# TermWylPomp1_rf.net
KiCad netlist of a schematic drawn in Altium Designer
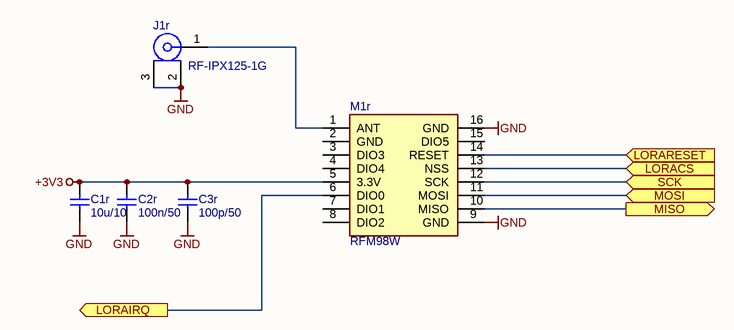
[diagram p0: TermWylPomp1_rf.SchDoc]

(export (version "E")
  (design (tool "Eeschema 10.0.6"))
  (components
    (comp (ref "C1r") (value "10u/10") (footprint "0805") (libsource (lib "PartsMySQL") (part "C")))
    (comp (ref "C2r") (value "100n/50") (footprint "0603-IPC") (libsource (lib "PartsMySQL") (part "C")))
    (comp (ref "C3r") (value "100p/50") (footprint "0603-IPC") (libsource (lib "PartsMySQL") (part "C")))
    (comp (ref "J1r")
      (value "RF-IPX125-1G")
      (footprint "HIROSE-UFL")
      (libsource (lib "PartsMySQL") (part "HIROSE-UFL"))
    )
    (comp (ref "M1r") (value "RFM98W") (footprint "RFM98W") (libsource (lib "PartsMySQL") (part "RFM98W")))
  )
  (nets
    (net (code "1") (name "+3V3") (class "Default")
      (node (ref "C1r") (pin "1") (pinfunction "1_1") (pintype "passive"))
      (node (ref "C2r") (pin "1") (pinfunction "1_1") (pintype "passive"))
      (node (ref "C3r") (pin "1") (pinfunction "1_1") (pintype "passive"))
      (node (ref "M1r") (pin "5") (pinfunction "3.3V_5") (pintype "passive"))
    )
    (net (code "2") (name "/LORACS") (class "Default")
      (node (ref "M1r") (pin "13") (pinfunction "NSS_13") (pintype "passive"))
    )
    (net (code "3") (name "/LORAIRQ") (class "Default")
      (node (ref "M1r") (pin "6") (pinfunction "DIO0_6") (pintype "passive"))
    )
    (net (code "4") (name "/LORARESET") (class "Default")
      (node (ref "M1r") (pin "14") (pinfunction "RESET_14") (pintype "passive"))
    )
    (net (code "5") (name "/MISO") (class "Default")
      (node (ref "M1r") (pin "10") (pinfunction "MISO_10") (pintype "passive"))
    )
    (net (code "6") (name "/MOSI") (class "Default")
      (node (ref "M1r") (pin "11") (pinfunction "MOSI_11") (pintype "passive"))
    )
    (net (code "7") (name "/SCK") (class "Default")
      (node (ref "M1r") (pin "12") (pinfunction "SCK_12") (pintype "passive"))
    )
    (net (code "8") (name "GND") (class "Default")
      (node (ref "C1r") (pin "2") (pinfunction "2_2") (pintype "passive"))
      (node (ref "C2r") (pin "2") (pinfunction "2_2") (pintype "passive"))
      (node (ref "C3r") (pin "2") (pinfunction "2_2") (pintype "passive"))
      (node (ref "J1r") (pin "2") (pinfunction "2_2") (pintype "passive"))
      (node (ref "J1r") (pin "3") (pinfunction "3_3") (pintype "passive"))
      (node (ref "M1r") (pin "16") (pinfunction "GND_16") (pintype "passive"))
      (node (ref "M1r") (pin "9") (pinfunction "GND_9") (pintype "passive"))
    )
    (net (code "9") (name "Net-(M1r-ANT)") (class "Default")
      (node (ref "J1r") (pin "1") (pinfunction "1_1") (pintype "passive"))
      (node (ref "M1r") (pin "1") (pinfunction "ANT_1") (pintype "passive"))
    )
    (net (code "10") (name "unconnected-(M1r-DIO1-Pad7)") (class "Default")
      (node (ref "M1r") (pin "7") (pinfunction "DIO1_7") (pintype "passive"))
    )
    (net (code "11") (name "unconnected-(M1r-DIO2-Pad8)") (class "Default")
      (node (ref "M1r") (pin "8") (pinfunction "DIO2_8") (pintype "passive"))
    )
    (net (code "12") (name "unconnected-(M1r-DIO3-Pad3)") (class "Default")
      (node (ref "M1r") (pin "3") (pinfunction "DIO3_3") (pintype "passive"))
    )
    (net (code "13") (name "unconnected-(M1r-DIO4-Pad4)") (class "Default")
      (node (ref "M1r") (pin "4") (pinfunction "DIO4_4") (pintype "passive"))
    )
    (net (code "14") (name "unconnected-(M1r-DIO5-Pad15)") (class "Default")
      (node (ref "M1r") (pin "15") (pinfunction "DIO5_15") (pintype "passive"))
    )
    (net (code "15") (name "unconnected-(M1r-GND-Pad2)") (class "Default")
      (node (ref "M1r") (pin "2") (pinfunction "GND_2") (pintype "passive"))
    )
  )
)
